# RHD2132_64CH.net
KiCad netlist of a schematic drawn in Altium Designer
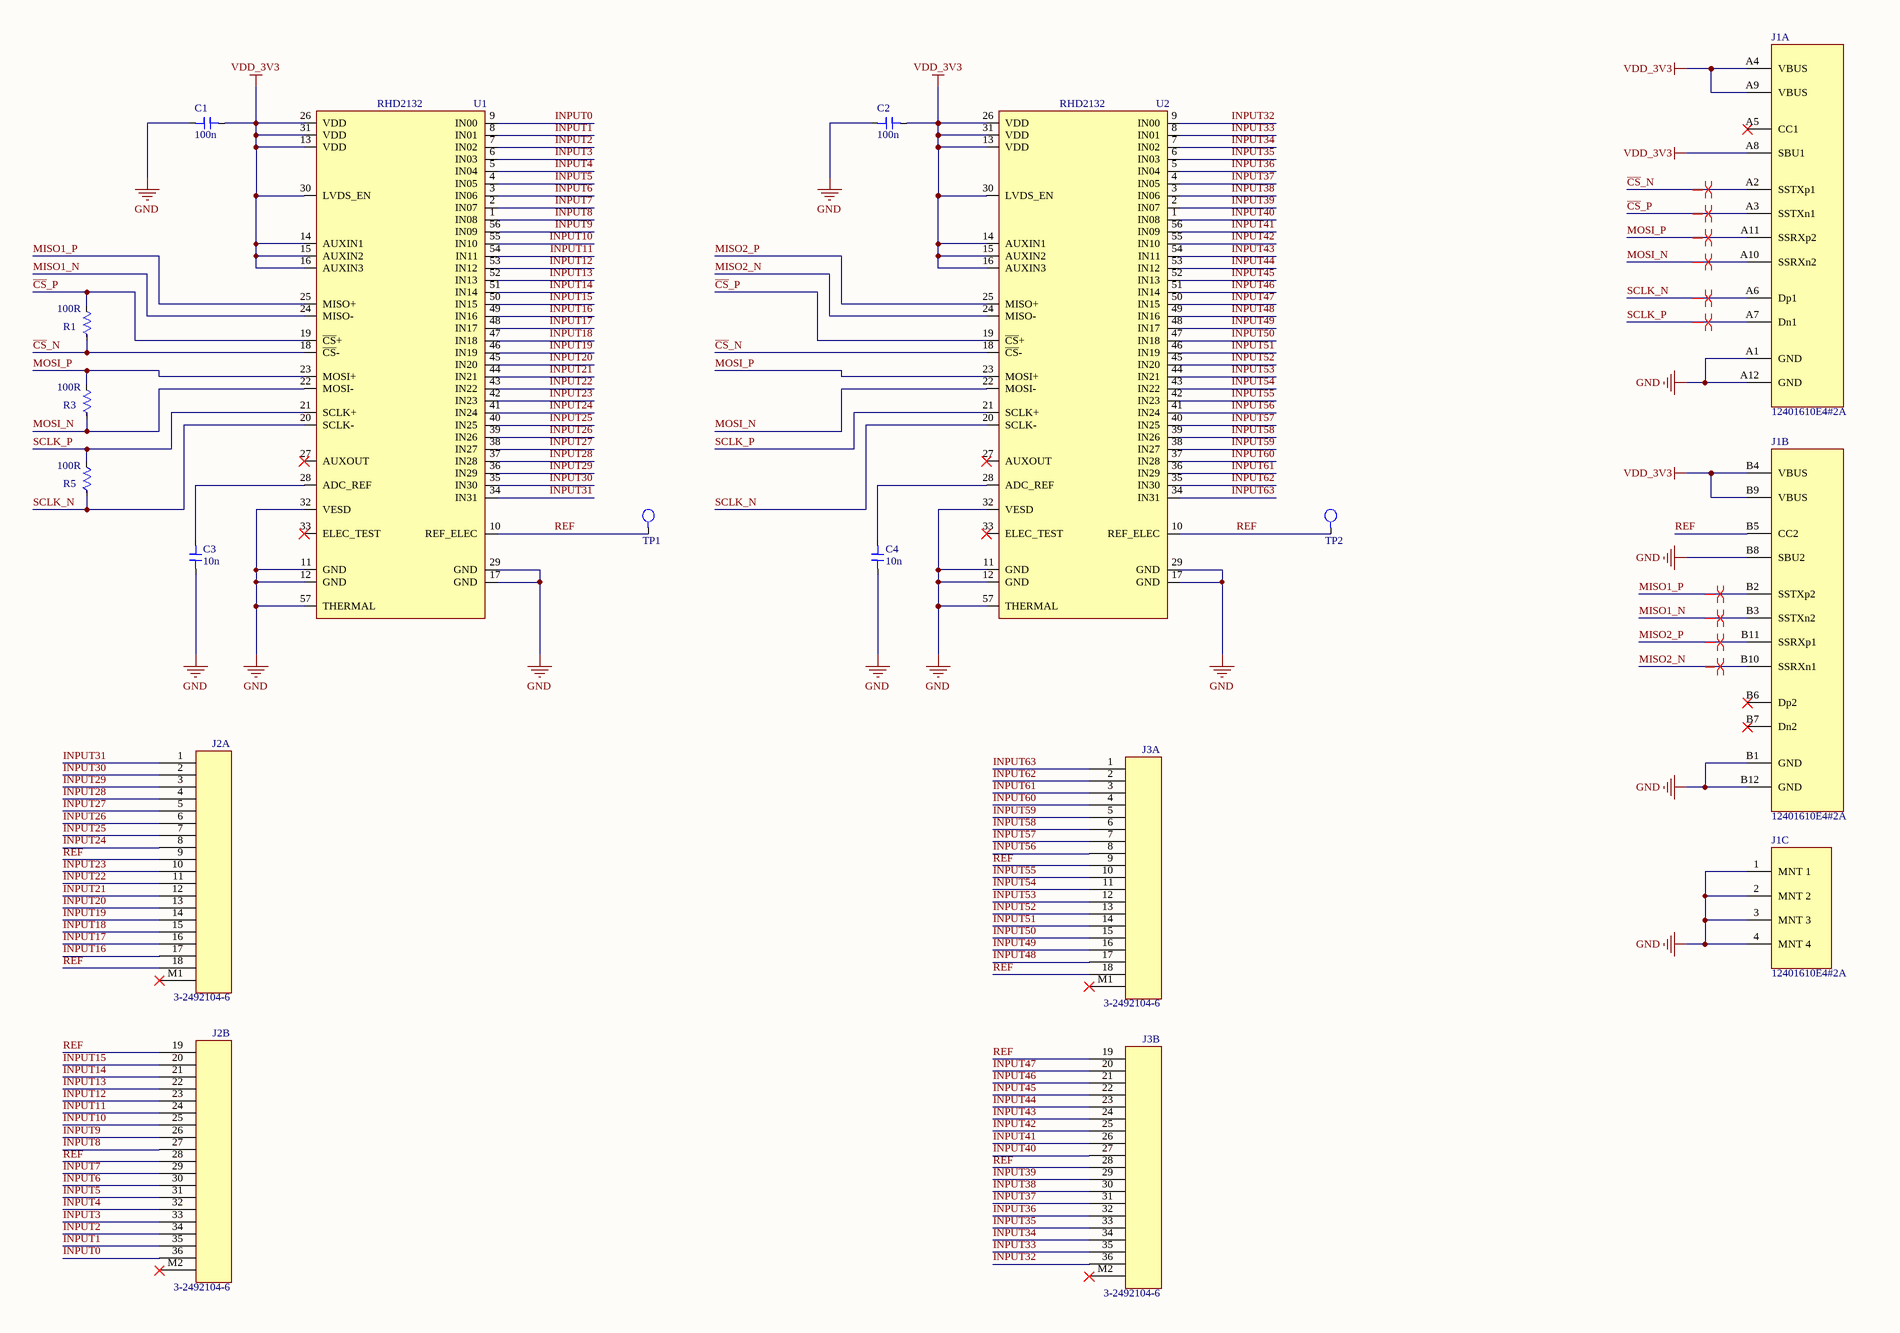
[diagram p0: RHD2132_64CH.SchDoc, left]
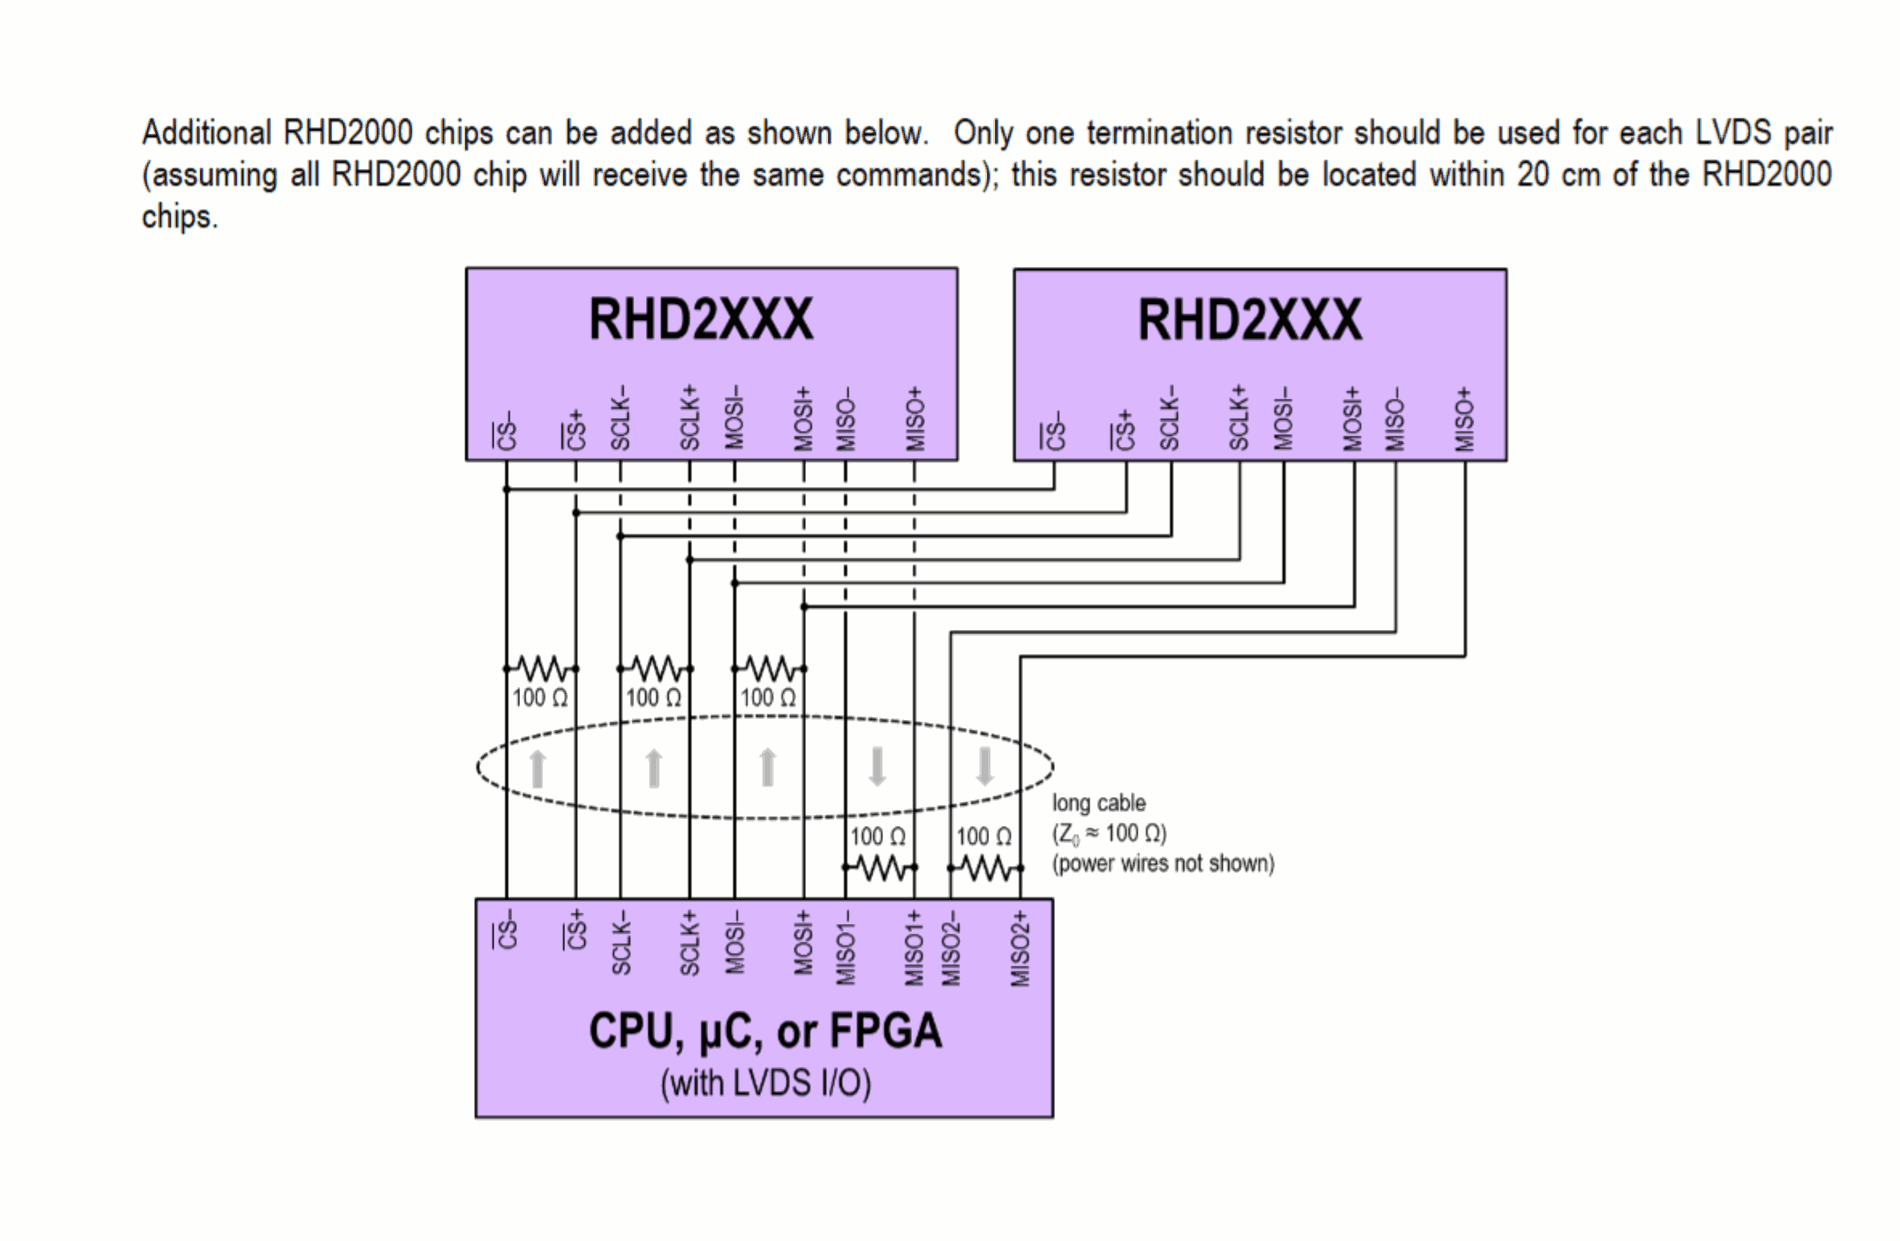
[diagram p1: RHD2132_64CH.SchDoc, right]

(export (version "E")
  (design (tool "Eeschema 10.0.6"))
  (components
    (comp (ref "C1")
      (value "100n")
      (footprint "0402_CAPACITOR")
      (description "Capacitor")
      (libsource (lib "UHDEMG") (part "Capacitor"))
    )
    (comp (ref "C2")
      (value "100n")
      (footprint "0402_CAPACITOR")
      (description "Capacitor")
      (libsource (lib "UHDEMG") (part "Capacitor"))
    )
    (comp (ref "C3")
      (value "10n")
      (footprint "0402_CAPACITOR")
      (description "Capacitor")
      (libsource (lib "UHDEMG") (part "Capacitor"))
    )
    (comp (ref "C4")
      (value "10n")
      (footprint "0402_CAPACITOR")
      (description "Capacitor")
      (libsource (lib "UHDEMG") (part "Capacitor"))
    )
    (comp (ref "J1")
      (value "12401610E4#2A")
      (footprint "CON_USB_C_SMD")
      (libsource (lib "UHDEMG") (part "CON_USBC_TH_SMT"))
    )
    (comp (ref "J2")
      (value "3-2492104-6")
      (footprint "CON_ZIF_RA_36POS")
      (description "36 Position FPC Connector Contacts, Bottom 0.020\" (0.50mm) Surface Mount, Right Angle")
      (libsource (lib "UHDEMG") (part "CON_ZIF_RA_36POS"))
    )
    (comp (ref "J3")
      (value "3-2492104-6")
      (footprint "CON_ZIF_RA_36POS")
      (description "36 Position FPC Connector Contacts, Bottom 0.020\" (0.50mm) Surface Mount, Right Angle")
      (libsource (lib "UHDEMG") (part "CON_ZIF_RA_36POS"))
    )
    (comp (ref "R1")
      (value "100R")
      (footprint "0402_Resistor")
      (description "Resistor")
      (libsource (lib "UHDEMG") (part "Resistor"))
    )
    (comp (ref "R3")
      (value "100R")
      (footprint "0402_Resistor")
      (description "Resistor")
      (libsource (lib "UHDEMG") (part "Resistor"))
    )
    (comp (ref "R5")
      (value "100R")
      (footprint "0402_Resistor")
      (description "Resistor")
      (libsource (lib "UHDEMG") (part "Resistor"))
    )
    (comp (ref "TP1")
      (value "TP_Small")
      (footprint "TP_Small_M2")
      (description "Through Hole Test Point - M2")
      (libsource (lib "UHDEMG") (part "TP_Small"))
    )
    (comp (ref "TP2")
      (value "TP_Small")
      (footprint "TP_Small_M2")
      (description "Through Hole Test Point - M2")
      (libsource (lib "UHDEMG") (part "TP_Small"))
    )
    (comp (ref "U1")
      (value "RHD2132")
      (footprint "QFN-56")
      (description "INTAN RHD2132 - 56-QFN")
      (libsource (lib "UHDEMG") (part "IC_RHD2132"))
    )
    (comp (ref "U2")
      (value "RHD2132")
      (footprint "QFN-56")
      (description "INTAN RHD2132 - 56-QFN")
      (libsource (lib "UHDEMG") (part "IC_RHD2132"))
    )
  )
  (nets
    (net (code "1") (name "/INPUT0") (class "Default")
      (node (ref "J2") (pin "36") (pinfunction "36_36") (pintype "passive"))
      (node (ref "U1") (pin "9") (pinfunction "IN00_9") (pintype "passive"))
    )
    (net (code "2") (name "/INPUT1") (class "Default")
      (node (ref "J2") (pin "35") (pinfunction "35_35") (pintype "passive"))
      (node (ref "U1") (pin "8") (pinfunction "IN01_8") (pintype "passive"))
    )
    (net (code "3") (name "/INPUT2") (class "Default")
      (node (ref "J2") (pin "34") (pinfunction "34_34") (pintype "passive"))
      (node (ref "U1") (pin "7") (pinfunction "IN02_7") (pintype "passive"))
    )
    (net (code "4") (name "/INPUT3") (class "Default")
      (node (ref "J2") (pin "33") (pinfunction "33_33") (pintype "passive"))
      (node (ref "U1") (pin "6") (pinfunction "IN03_6") (pintype "passive"))
    )
    (net (code "5") (name "/INPUT4") (class "Default")
      (node (ref "J2") (pin "32") (pinfunction "32_32") (pintype "passive"))
      (node (ref "U1") (pin "5") (pinfunction "IN04_5") (pintype "passive"))
    )
    (net (code "6") (name "/INPUT5") (class "Default")
      (node (ref "J2") (pin "31") (pinfunction "31_31") (pintype "passive"))
      (node (ref "U1") (pin "4") (pinfunction "IN05_4") (pintype "passive"))
    )
    (net (code "7") (name "/INPUT6") (class "Default")
      (node (ref "J2") (pin "30") (pinfunction "30_30") (pintype "passive"))
      (node (ref "U1") (pin "3") (pinfunction "IN06_3") (pintype "passive"))
    )
    (net (code "8") (name "/INPUT7") (class "Default")
      (node (ref "J2") (pin "29") (pinfunction "29_29") (pintype "passive"))
      (node (ref "U1") (pin "2") (pinfunction "IN07_2") (pintype "passive"))
    )
    (net (code "9") (name "/INPUT8") (class "Default")
      (node (ref "J2") (pin "27") (pinfunction "27_27") (pintype "passive"))
      (node (ref "U1") (pin "1") (pinfunction "IN08_1") (pintype "passive"))
    )
    (net (code "10") (name "/INPUT9") (class "Default")
      (node (ref "J2") (pin "26") (pinfunction "26_26") (pintype "passive"))
      (node (ref "U1") (pin "56") (pinfunction "IN09_56") (pintype "passive"))
    )
    (net (code "11") (name "/INPUT10") (class "Default")
      (node (ref "J2") (pin "25") (pinfunction "25_25") (pintype "passive"))
      (node (ref "U1") (pin "55") (pinfunction "IN10_55") (pintype "passive"))
    )
    (net (code "12") (name "/INPUT11") (class "Default")
      (node (ref "J2") (pin "24") (pinfunction "24_24") (pintype "passive"))
      (node (ref "U1") (pin "54") (pinfunction "IN11_54") (pintype "passive"))
    )
    (net (code "13") (name "/INPUT12") (class "Default")
      (node (ref "J2") (pin "23") (pinfunction "23_23") (pintype "passive"))
      (node (ref "U1") (pin "53") (pinfunction "IN12_53") (pintype "passive"))
    )
    (net (code "14") (name "/INPUT13") (class "Default")
      (node (ref "J2") (pin "22") (pinfunction "22_22") (pintype "passive"))
      (node (ref "U1") (pin "52") (pinfunction "IN13_52") (pintype "passive"))
    )
    (net (code "15") (name "/INPUT14") (class "Default")
      (node (ref "J2") (pin "21") (pinfunction "21_21") (pintype "passive"))
      (node (ref "U1") (pin "51") (pinfunction "IN14_51") (pintype "passive"))
    )
    (net (code "16") (name "/INPUT15") (class "Default")
      (node (ref "J2") (pin "20") (pinfunction "20_20") (pintype "passive"))
      (node (ref "U1") (pin "50") (pinfunction "IN15_50") (pintype "passive"))
    )
    (net (code "17") (name "/INPUT16") (class "Default")
      (node (ref "J2") (pin "17") (pinfunction "17_17") (pintype "passive"))
      (node (ref "U1") (pin "49") (pinfunction "IN16_49") (pintype "passive"))
    )
    (net (code "18") (name "/INPUT17") (class "Default")
      (node (ref "J2") (pin "16") (pinfunction "16_16") (pintype "passive"))
      (node (ref "U1") (pin "48") (pinfunction "IN17_48") (pintype "passive"))
    )
    (net (code "19") (name "/INPUT18") (class "Default")
      (node (ref "J2") (pin "15") (pinfunction "15_15") (pintype "passive"))
      (node (ref "U1") (pin "47") (pinfunction "IN18_47") (pintype "passive"))
    )
    (net (code "20") (name "/INPUT19") (class "Default")
      (node (ref "J2") (pin "14") (pinfunction "14_14") (pintype "passive"))
      (node (ref "U1") (pin "46") (pinfunction "IN19_46") (pintype "passive"))
    )
    (net (code "21") (name "/INPUT20") (class "Default")
      (node (ref "J2") (pin "13") (pinfunction "13_13") (pintype "passive"))
      (node (ref "U1") (pin "45") (pinfunction "IN20_45") (pintype "passive"))
    )
    (net (code "22") (name "/INPUT21") (class "Default")
      (node (ref "J2") (pin "12") (pinfunction "12_12") (pintype "passive"))
      (node (ref "U1") (pin "44") (pinfunction "IN21_44") (pintype "passive"))
    )
    (net (code "23") (name "/INPUT22") (class "Default")
      (node (ref "J2") (pin "11") (pinfunction "11_11") (pintype "passive"))
      (node (ref "U1") (pin "43") (pinfunction "IN22_43") (pintype "passive"))
    )
    (net (code "24") (name "/INPUT23") (class "Default")
      (node (ref "J2") (pin "10") (pinfunction "10_10") (pintype "passive"))
      (node (ref "U1") (pin "42") (pinfunction "IN23_42") (pintype "passive"))
    )
    (net (code "25") (name "/INPUT24") (class "Default")
      (node (ref "J2") (pin "8") (pinfunction "8_8") (pintype "passive"))
      (node (ref "U1") (pin "41") (pinfunction "IN24_41") (pintype "passive"))
    )
    (net (code "26") (name "/INPUT25") (class "Default")
      (node (ref "J2") (pin "7") (pinfunction "7_7") (pintype "passive"))
      (node (ref "U1") (pin "40") (pinfunction "IN25_40") (pintype "passive"))
    )
    (net (code "27") (name "/INPUT26") (class "Default")
      (node (ref "J2") (pin "6") (pinfunction "6_6") (pintype "passive"))
      (node (ref "U1") (pin "39") (pinfunction "IN26_39") (pintype "passive"))
    )
    (net (code "28") (name "/INPUT27") (class "Default")
      (node (ref "J2") (pin "5") (pinfunction "5_5") (pintype "passive"))
      (node (ref "U1") (pin "38") (pinfunction "IN27_38") (pintype "passive"))
    )
    (net (code "29") (name "/INPUT28") (class "Default")
      (node (ref "J2") (pin "4") (pinfunction "4_4") (pintype "passive"))
      (node (ref "U1") (pin "37") (pinfunction "IN28_37") (pintype "passive"))
    )
    (net (code "30") (name "/INPUT29") (class "Default")
      (node (ref "J2") (pin "3") (pinfunction "3_3") (pintype "passive"))
      (node (ref "U1") (pin "36") (pinfunction "IN29_36") (pintype "passive"))
    )
    (net (code "31") (name "/INPUT30") (class "Default")
      (node (ref "J2") (pin "2") (pinfunction "2_2") (pintype "passive"))
      (node (ref "U1") (pin "35") (pinfunction "IN30_35") (pintype "passive"))
    )
    (net (code "32") (name "/INPUT31") (class "Default")
      (node (ref "J2") (pin "1") (pinfunction "1_1") (pintype "passive"))
      (node (ref "U1") (pin "34") (pinfunction "IN31_34") (pintype "passive"))
    )
    (net (code "33") (name "/INPUT32") (class "Default")
      (node (ref "J3") (pin "36") (pinfunction "36_36") (pintype "passive"))
      (node (ref "U2") (pin "9") (pinfunction "IN00_9") (pintype "passive"))
    )
    (net (code "34") (name "/INPUT33") (class "Default")
      (node (ref "J3") (pin "35") (pinfunction "35_35") (pintype "passive"))
      (node (ref "U2") (pin "8") (pinfunction "IN01_8") (pintype "passive"))
    )
    (net (code "35") (name "/INPUT34") (class "Default")
      (node (ref "J3") (pin "34") (pinfunction "34_34") (pintype "passive"))
      (node (ref "U2") (pin "7") (pinfunction "IN02_7") (pintype "passive"))
    )
    (net (code "36") (name "/INPUT35") (class "Default")
      (node (ref "J3") (pin "33") (pinfunction "33_33") (pintype "passive"))
      (node (ref "U2") (pin "6") (pinfunction "IN03_6") (pintype "passive"))
    )
    (net (code "37") (name "/INPUT36") (class "Default")
      (node (ref "J3") (pin "32") (pinfunction "32_32") (pintype "passive"))
      (node (ref "U2") (pin "5") (pinfunction "IN04_5") (pintype "passive"))
    )
    (net (code "38") (name "/INPUT37") (class "Default")
      (node (ref "J3") (pin "31") (pinfunction "31_31") (pintype "passive"))
      (node (ref "U2") (pin "4") (pinfunction "IN05_4") (pintype "passive"))
    )
    (net (code "39") (name "/INPUT38") (class "Default")
      (node (ref "J3") (pin "30") (pinfunction "30_30") (pintype "passive"))
      (node (ref "U2") (pin "3") (pinfunction "IN06_3") (pintype "passive"))
    )
    (net (code "40") (name "/INPUT39") (class "Default")
      (node (ref "J3") (pin "29") (pinfunction "29_29") (pintype "passive"))
      (node (ref "U2") (pin "2") (pinfunction "IN07_2") (pintype "passive"))
    )
    (net (code "41") (name "/INPUT40") (class "Default")
      (node (ref "J3") (pin "27") (pinfunction "27_27") (pintype "passive"))
      (node (ref "U2") (pin "1") (pinfunction "IN08_1") (pintype "passive"))
    )
    (net (code "42") (name "/INPUT41") (class "Default")
      (node (ref "J3") (pin "26") (pinfunction "26_26") (pintype "passive"))
      (node (ref "U2") (pin "56") (pinfunction "IN09_56") (pintype "passive"))
    )
    (net (code "43") (name "/INPUT42") (class "Default")
      (node (ref "J3") (pin "25") (pinfunction "25_25") (pintype "passive"))
      (node (ref "U2") (pin "55") (pinfunction "IN10_55") (pintype "passive"))
    )
    (net (code "44") (name "/INPUT43") (class "Default")
      (node (ref "J3") (pin "24") (pinfunction "24_24") (pintype "passive"))
      (node (ref "U2") (pin "54") (pinfunction "IN11_54") (pintype "passive"))
    )
    (net (code "45") (name "/INPUT44") (class "Default")
      (node (ref "J3") (pin "23") (pinfunction "23_23") (pintype "passive"))
      (node (ref "U2") (pin "53") (pinfunction "IN12_53") (pintype "passive"))
    )
    (net (code "46") (name "/INPUT45") (class "Default")
      (node (ref "J3") (pin "22") (pinfunction "22_22") (pintype "passive"))
      (node (ref "U2") (pin "52") (pinfunction "IN13_52") (pintype "passive"))
    )
    (net (code "47") (name "/INPUT46") (class "Default")
      (node (ref "J3") (pin "21") (pinfunction "21_21") (pintype "passive"))
      (node (ref "U2") (pin "51") (pinfunction "IN14_51") (pintype "passive"))
    )
    (net (code "48") (name "/INPUT47") (class "Default")
      (node (ref "J3") (pin "20") (pinfunction "20_20") (pintype "passive"))
      (node (ref "U2") (pin "50") (pinfunction "IN15_50") (pintype "passive"))
    )
    (net (code "49") (name "/INPUT48") (class "Default")
      (node (ref "J3") (pin "17") (pinfunction "17_17") (pintype "passive"))
      (node (ref "U2") (pin "49") (pinfunction "IN16_49") (pintype "passive"))
    )
    (net (code "50") (name "/INPUT49") (class "Default")
      (node (ref "J3") (pin "16") (pinfunction "16_16") (pintype "passive"))
      (node (ref "U2") (pin "48") (pinfunction "IN17_48") (pintype "passive"))
    )
    (net (code "51") (name "/INPUT50") (class "Default")
      (node (ref "J3") (pin "15") (pinfunction "15_15") (pintype "passive"))
      (node (ref "U2") (pin "47") (pinfunction "IN18_47") (pintype "passive"))
    )
    (net (code "52") (name "/INPUT51") (class "Default")
      (node (ref "J3") (pin "14") (pinfunction "14_14") (pintype "passive"))
      (node (ref "U2") (pin "46") (pinfunction "IN19_46") (pintype "passive"))
    )
    (net (code "53") (name "/INPUT52") (class "Default")
      (node (ref "J3") (pin "13") (pinfunction "13_13") (pintype "passive"))
      (node (ref "U2") (pin "45") (pinfunction "IN20_45") (pintype "passive"))
    )
    (net (code "54") (name "/INPUT53") (class "Default")
      (node (ref "J3") (pin "12") (pinfunction "12_12") (pintype "passive"))
      (node (ref "U2") (pin "44") (pinfunction "IN21_44") (pintype "passive"))
    )
    (net (code "55") (name "/INPUT54") (class "Default")
      (node (ref "J3") (pin "11") (pinfunction "11_11") (pintype "passive"))
      (node (ref "U2") (pin "43") (pinfunction "IN22_43") (pintype "passive"))
    )
    (net (code "56") (name "/INPUT55") (class "Default")
      (node (ref "J3") (pin "10") (pinfunction "10_10") (pintype "passive"))
      (node (ref "U2") (pin "42") (pinfunction "IN23_42") (pintype "passive"))
    )
    (net (code "57") (name "/INPUT56") (class "Default")
      (node (ref "J3") (pin "8") (pinfunction "8_8") (pintype "passive"))
      (node (ref "U2") (pin "41") (pinfunction "IN24_41") (pintype "passive"))
    )
    (net (code "58") (name "/INPUT57") (class "Default")
      (node (ref "J3") (pin "7") (pinfunction "7_7") (pintype "passive"))
      (node (ref "U2") (pin "40") (pinfunction "IN25_40") (pintype "passive"))
    )
    (net (code "59") (name "/INPUT58") (class "Default")
      (node (ref "J3") (pin "6") (pinfunction "6_6") (pintype "passive"))
      (node (ref "U2") (pin "39") (pinfunction "IN26_39") (pintype "passive"))
    )
    (net (code "60") (name "/INPUT59") (class "Default")
      (node (ref "J3") (pin "5") (pinfunction "5_5") (pintype "passive"))
      (node (ref "U2") (pin "38") (pinfunction "IN27_38") (pintype "passive"))
    )
    (net (code "61") (name "/INPUT60") (class "Default")
      (node (ref "J3") (pin "4") (pinfunction "4_4") (pintype "passive"))
      (node (ref "U2") (pin "37") (pinfunction "IN28_37") (pintype "passive"))
    )
    (net (code "62") (name "/INPUT61") (class "Default")
      (node (ref "J3") (pin "3") (pinfunction "3_3") (pintype "passive"))
      (node (ref "U2") (pin "36") (pinfunction "IN29_36") (pintype "passive"))
    )
    (net (code "63") (name "/INPUT62") (class "Default")
      (node (ref "J3") (pin "2") (pinfunction "2_2") (pintype "passive"))
      (node (ref "U2") (pin "35") (pinfunction "IN30_35") (pintype "passive"))
    )
    (net (code "64") (name "/INPUT63") (class "Default")
      (node (ref "J3") (pin "1") (pinfunction "1_1") (pintype "passive"))
      (node (ref "U2") (pin "34") (pinfunction "IN31_34") (pintype "passive"))
    )
    (net (code "65") (name "/MISO1_N") (class "Default")
      (node (ref "J1") (pin "B3") (pinfunction "SSTXn2_B3") (pintype "passive"))
      (node (ref "U1") (pin "24") (pinfunction "MISO-_24") (pintype "passive"))
    )
    (net (code "66") (name "/MISO1_P") (class "Default")
      (node (ref "J1") (pin "B2") (pinfunction "SSTXp2_B2") (pintype "passive"))
      (node (ref "U1") (pin "25") (pinfunction "MISO+_25") (pintype "passive"))
    )
    (net (code "67") (name "/MISO2_N") (class "Default")
      (node (ref "J1") (pin "B10") (pinfunction "SSRXn1_B10") (pintype "passive"))
      (node (ref "U2") (pin "24") (pinfunction "MISO-_24") (pintype "passive"))
    )
    (net (code "68") (name "/MISO2_P") (class "Default")
      (node (ref "J1") (pin "B11") (pinfunction "SSRXp1_B11") (pintype "passive"))
      (node (ref "U2") (pin "25") (pinfunction "MISO+_25") (pintype "passive"))
    )
    (net (code "69") (name "/MOSI_N") (class "Default")
      (node (ref "J1") (pin "A10") (pinfunction "SSRXn2_A10") (pintype "passive"))
      (node (ref "R3") (pin "1") (pinfunction "1_1") (pintype "passive"))
      (node (ref "U1") (pin "22") (pinfunction "MOSI-_22") (pintype "passive"))
      (node (ref "U2") (pin "22") (pinfunction "MOSI-_22") (pintype "passive"))
    )
    (net (code "70") (name "/MOSI_P") (class "Default")
      (node (ref "J1") (pin "A11") (pinfunction "SSRXp2_A11") (pintype "passive"))
      (node (ref "R3") (pin "2") (pinfunction "2_2") (pintype "passive"))
      (node (ref "U1") (pin "23") (pinfunction "MOSI+_23") (pintype "passive"))
      (node (ref "U2") (pin "23") (pinfunction "MOSI+_23") (pintype "passive"))
    )
    (net (code "71") (name "/REF") (class "Default")
      (node (ref "J1") (pin "B5") (pinfunction "CC2_B5") (pintype "passive"))
      (node (ref "J2") (pin "18") (pinfunction "18_18") (pintype "passive"))
      (node (ref "J2") (pin "19") (pinfunction "19_19") (pintype "passive"))
      (node (ref "J2") (pin "28") (pinfunction "28_28") (pintype "passive"))
      (node (ref "J2") (pin "9") (pinfunction "9_9") (pintype "passive"))
      (node (ref "J3") (pin "18") (pinfunction "18_18") (pintype "passive"))
      (node (ref "J3") (pin "19") (pinfunction "19_19") (pintype "passive"))
      (node (ref "J3") (pin "28") (pinfunction "28_28") (pintype "passive"))
      (node (ref "J3") (pin "9") (pinfunction "9_9") (pintype "passive"))
      (node (ref "TP1") (pin "1") (pinfunction "1_1") (pintype "passive"))
      (node (ref "TP2") (pin "1") (pinfunction "1_1") (pintype "passive"))
      (node (ref "U1") (pin "10") (pinfunction "REF_ELEC_10") (pintype "passive"))
      (node (ref "U2") (pin "10") (pinfunction "REF_ELEC_10") (pintype "passive"))
    )
    (net (code "72") (name "/SCLK_N") (class "Default")
      (node (ref "J1") (pin "A6") (pinfunction "Dp1_A6") (pintype "passive"))
      (node (ref "R5") (pin "1") (pinfunction "1_1") (pintype "passive"))
      (node (ref "U1") (pin "20") (pinfunction "SCLK-_20") (pintype "passive"))
      (node (ref "U2") (pin "20") (pinfunction "SCLK-_20") (pintype "passive"))
    )
    (net (code "73") (name "/SCLK_P") (class "Default")
      (node (ref "J1") (pin "A7") (pinfunction "Dn1_A7") (pintype "passive"))
      (node (ref "R5") (pin "2") (pinfunction "2_2") (pintype "passive"))
      (node (ref "U1") (pin "21") (pinfunction "SCLK+_21") (pintype "passive"))
      (node (ref "U2") (pin "21") (pinfunction "SCLK+_21") (pintype "passive"))
    )
    (net (code "74") (name "/~{CS}_N") (class "Default")
      (node (ref "J1") (pin "A2") (pinfunction "SSTXp1_A2") (pintype "passive"))
      (node (ref "R1") (pin "1") (pinfunction "1_1") (pintype "passive"))
      (node (ref "U1") (pin "18") (pinfunction "~{CS}-_18") (pintype "passive"))
      (node (ref "U2") (pin "18") (pinfunction "~{CS}-_18") (pintype "passive"))
    )
    (net (code "75") (name "/~{CS}_P") (class "Default")
      (node (ref "J1") (pin "A3") (pinfunction "SSTXn1_A3") (pintype "passive"))
      (node (ref "R1") (pin "2") (pinfunction "2_2") (pintype "passive"))
      (node (ref "U1") (pin "19") (pinfunction "~{CS}+_19") (pintype "passive"))
      (node (ref "U2") (pin "19") (pinfunction "~{CS}+_19") (pintype "passive"))
    )
    (net (code "76") (name "GND") (class "Default")
      (node (ref "C1") (pin "1") (pinfunction "1_1") (pintype "passive"))
      (node (ref "C2") (pin "1") (pinfunction "1_1") (pintype "passive"))
      (node (ref "C3") (pin "1") (pinfunction "1_1") (pintype "passive"))
      (node (ref "C4") (pin "1") (pinfunction "1_1") (pintype "passive"))
      (node (ref "J1") (pin "1") (pinfunction "MNT_1_1") (pintype "passive"))
      (node (ref "J1") (pin "2") (pinfunction "MNT_2_2") (pintype "passive"))
      (node (ref "J1") (pin "3") (pinfunction "MNT_3_3") (pintype "passive"))
      (node (ref "J1") (pin "4") (pinfunction "MNT_4_4") (pintype "passive"))
      (node (ref "J1") (pin "A1") (pinfunction "GND_A1") (pintype "passive"))
      (node (ref "J1") (pin "A12") (pinfunction "GND_A12") (pintype "passive"))
      (node (ref "J1") (pin "B1") (pinfunction "GND_B1") (pintype "passive"))
      (node (ref "J1") (pin "B12") (pinfunction "GND_B12") (pintype "passive"))
      (node (ref "J1") (pin "B8") (pinfunction "SBU2_B8") (pintype "passive"))
      (node (ref "U1") (pin "11") (pinfunction "GND_11") (pintype "passive"))
      (node (ref "U1") (pin "12") (pinfunction "GND_12") (pintype "passive"))
      (node (ref "U1") (pin "17") (pinfunction "GND_17") (pintype "passive"))
      (node (ref "U1") (pin "29") (pinfunction "GND_29") (pintype "passive"))
      (node (ref "U1") (pin "32") (pinfunction "VESD_32") (pintype "passive"))
      (node (ref "U1") (pin "57") (pinfunction "THERMAL_57") (pintype "passive"))
      (node (ref "U2") (pin "11") (pinfunction "GND_11") (pintype "passive"))
      (node (ref "U2") (pin "12") (pinfunction "GND_12") (pintype "passive"))
      (node (ref "U2") (pin "17") (pinfunction "GND_17") (pintype "passive"))
      (node (ref "U2") (pin "29") (pinfunction "GND_29") (pintype "passive"))
      (node (ref "U2") (pin "32") (pinfunction "VESD_32") (pintype "passive"))
      (node (ref "U2") (pin "57") (pinfunction "THERMAL_57") (pintype "passive"))
    )
    (net (code "77") (name "Net-(U1-ADC_REF)") (class "Default")
      (node (ref "C3") (pin "2") (pinfunction "2_2") (pintype "passive"))
      (node (ref "U1") (pin "28") (pinfunction "ADC_REF_28") (pintype "passive"))
    )
    (net (code "78") (name "Net-(U2-ADC_REF)") (class "Default")
      (node (ref "C4") (pin "2") (pinfunction "2_2") (pintype "passive"))
      (node (ref "U2") (pin "28") (pinfunction "ADC_REF_28") (pintype "passive"))
    )
    (net (code "79") (name "VDD_3V3") (class "Default")
      (node (ref "C1") (pin "2") (pinfunction "2_2") (pintype "passive"))
      (node (ref "C2") (pin "2") (pinfunction "2_2") (pintype "passive"))
      (node (ref "J1") (pin "A4") (pinfunction "VBUS_A4") (pintype "passive"))
      (node (ref "J1") (pin "A8") (pinfunction "SBU1_A8") (pintype "passive"))
      (node (ref "J1") (pin "A9") (pinfunction "VBUS_A9") (pintype "passive"))
      (node (ref "J1") (pin "B4") (pinfunction "VBUS_B4") (pintype "passive"))
      (node (ref "J1") (pin "B9") (pinfunction "VBUS_B9") (pintype "passive"))
      (node (ref "U1") (pin "13") (pinfunction "VDD_13") (pintype "passive"))
      (node (ref "U1") (pin "14") (pinfunction "AUXIN1_14") (pintype "passive"))
      (node (ref "U1") (pin "15") (pinfunction "AUXIN2_15") (pintype "passive"))
      (node (ref "U1") (pin "16") (pinfunction "AUXIN3_16") (pintype "passive"))
      (node (ref "U1") (pin "26") (pinfunction "VDD_26") (pintype "passive"))
      (node (ref "U1") (pin "30") (pinfunction "LVDS_EN_30") (pintype "passive"))
      (node (ref "U1") (pin "31") (pinfunction "VDD_31") (pintype "passive"))
      (node (ref "U2") (pin "13") (pinfunction "VDD_13") (pintype "passive"))
      (node (ref "U2") (pin "14") (pinfunction "AUXIN1_14") (pintype "passive"))
      (node (ref "U2") (pin "15") (pinfunction "AUXIN2_15") (pintype "passive"))
      (node (ref "U2") (pin "16") (pinfunction "AUXIN3_16") (pintype "passive"))
      (node (ref "U2") (pin "26") (pinfunction "VDD_26") (pintype "passive"))
      (node (ref "U2") (pin "30") (pinfunction "LVDS_EN_30") (pintype "passive"))
      (node (ref "U2") (pin "31") (pinfunction "VDD_31") (pintype "passive"))
    )
    (net (code "80") (name "unconnected-(J1A-CC1-PadA5)") (class "Default")
      (node (ref "J1") (pin "A5") (pinfunction "CC1_A5") (pintype "passive+no_connect"))
    )
    (net (code "81") (name "unconnected-(J1B-Dn2-PadB7)") (class "Default")
      (node (ref "J1") (pin "B7") (pinfunction "Dn2_B7") (pintype "passive+no_connect"))
    )
    (net (code "82") (name "unconnected-(J1B-Dp2-PadB6)") (class "Default")
      (node (ref "J1") (pin "B6") (pinfunction "Dp2_B6") (pintype "passive+no_connect"))
    )
    (net (code "83") (name "unconnected-(J2-PadM1)") (class "Default")
      (node (ref "J2") (pin "M1") (pinfunction "M1_M1") (pintype "passive+no_connect"))
    )
    (net (code "84") (name "unconnected-(J2-PadM2)") (class "Default")
      (node (ref "J2") (pin "M2") (pinfunction "M2_M2") (pintype "passive+no_connect"))
    )
    (net (code "85") (name "unconnected-(J3-PadM1)") (class "Default")
      (node (ref "J3") (pin "M1") (pinfunction "M1_M1") (pintype "passive+no_connect"))
    )
    (net (code "86") (name "unconnected-(J3-PadM2)") (class "Default")
      (node (ref "J3") (pin "M2") (pinfunction "M2_M2") (pintype "passive+no_connect"))
    )
    (net (code "87") (name "unconnected-(U1-AUXOUT-Pad27)") (class "Default")
      (node (ref "U1") (pin "27") (pinfunction "AUXOUT_27") (pintype "passive+no_connect"))
    )
    (net (code "88") (name "unconnected-(U1-ELEC_TEST-Pad33)") (class "Default")
      (node (ref "U1") (pin "33") (pinfunction "ELEC_TEST_33") (pintype "passive+no_connect"))
    )
    (net (code "89") (name "unconnected-(U2-AUXOUT-Pad27)") (class "Default")
      (node (ref "U2") (pin "27") (pinfunction "AUXOUT_27") (pintype "passive+no_connect"))
    )
    (net (code "90") (name "unconnected-(U2-ELEC_TEST-Pad33)") (class "Default")
      (node (ref "U2") (pin "33") (pinfunction "ELEC_TEST_33") (pintype "passive+no_connect"))
    )
  )
)
